# Flasher_2Ch_ISO_Astable.net
KiCad netlist of a schematic drawn in Altium Designer
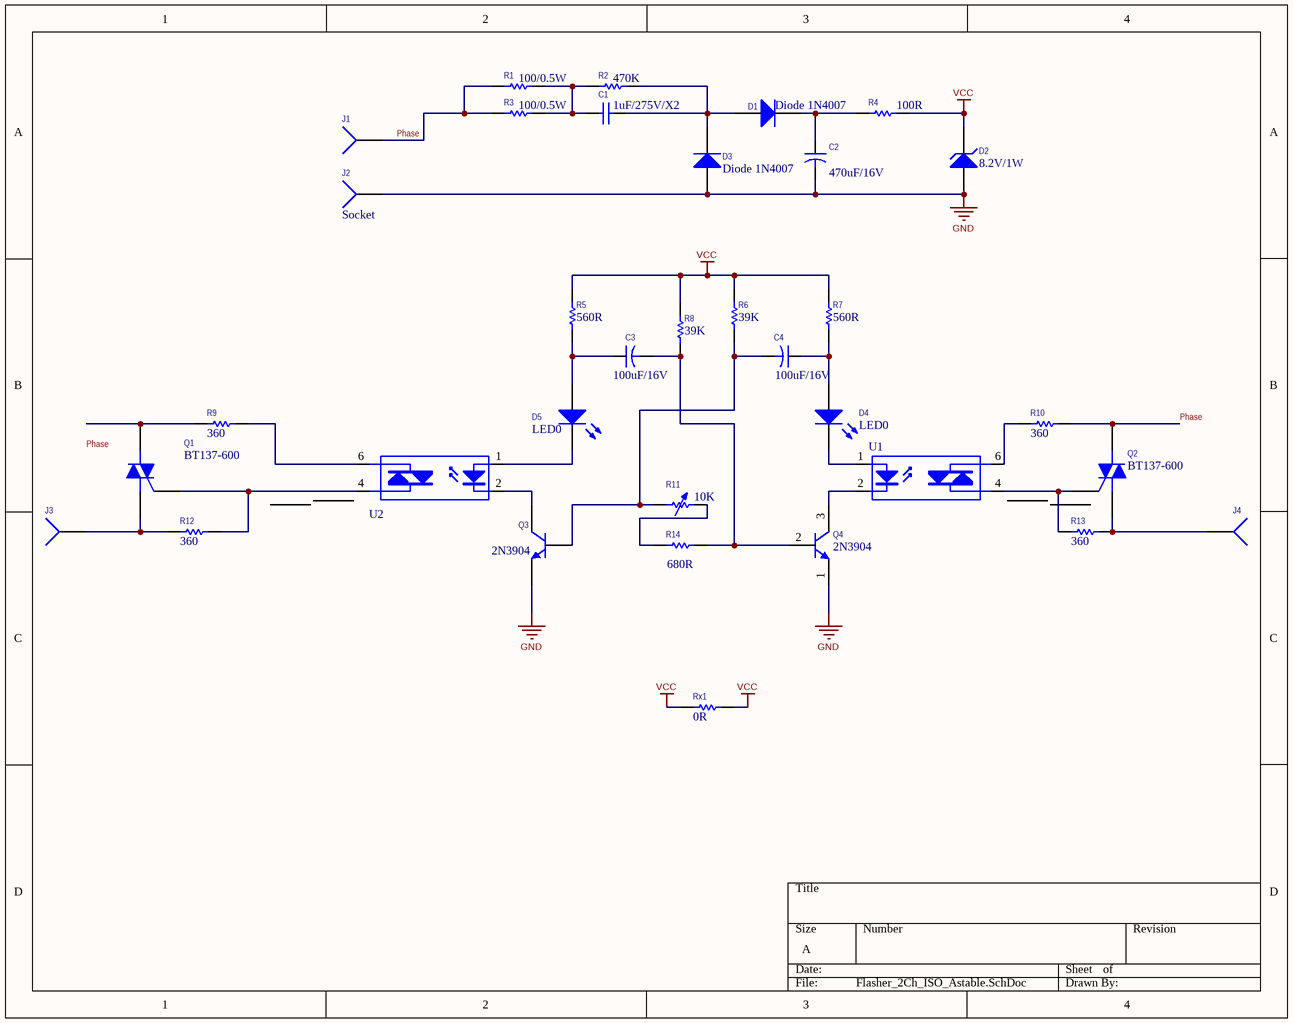
[diagram p0: Flasher_2Ch_ISO_Astable.SchDoc]

(export (version "E")
  (design (tool "Eeschema 10.0.6"))
  (components
    (comp (ref "C1")
      (value "1uF/275V/X2")
      (footprint "Cap_polyester_275V_P22.5")
      (description "Capacitor")
      (fields (field (name "Comment") "Cap") (field (name "PUBLISHER") "Altium Limited"))
      (libsource (lib "Miscellaneous Devices") (part "Cap"))
    )
    (comp (ref "C2")
      (value "470uF/16V")
      (footprint "Cap electrolitic radial 8x12-3.5")
      (description "Capacitor")
      (fields (field (name "Comment") "Cap2") (field (name "PUBLISHER") "Altium Limited"))
      (libsource (lib "Miscellaneous Devices") (part "Cap2"))
    )
    (comp (ref "C3")
      (value "100uF/16V")
      (footprint "Cap electrolitic radial 5x11-2")
      (description "Capacitor")
      (fields (field (name "Comment") "Cap2") (field (name "PUBLISHER") "Altium Limited"))
      (libsource (lib "Miscellaneous Devices") (part "Cap2"))
    )
    (comp (ref "C4")
      (value "100uF/16V")
      (footprint "Cap electrolitic radial 5x11-2")
      (description "Capacitor")
      (fields (field (name "Comment") "Cap2") (field (name "PUBLISHER") "Altium Limited"))
      (libsource (lib "Miscellaneous Devices") (part "Cap2"))
    )
    (comp (ref "D1")
      (value "Diode 1N4007")
      (footprint "DO-204AL")
      (description "1 Amp General Purpose Rectifier")
      (fields (field (name "PUBLISHER") "Altium Limited"))
      (libsource (lib "Miscellaneous Devices") (part "Diode 1N4007"))
    )
    (comp (ref "D2")
      (value "8.2V/1W")
      (footprint "DO-204AL")
      (description "Zener Diode")
      (fields (field (name "PUBLISHER") "Altium Limited"))
      (libsource (lib "Miscellaneous Devices") (part "D Zener"))
    )
    (comp (ref "D3")
      (value "Diode 1N4007")
      (footprint "DO-204AL")
      (description "1 Amp General Purpose Rectifier")
      (fields (field (name "PUBLISHER") "Altium Limited"))
      (libsource (lib "Miscellaneous Devices") (part "Diode 1N4007"))
    )
    (comp (ref "D4")
      (value "LED0")
      (footprint "LED5MM_RED")
      (description "Typical INFRARED GaAs LED")
      (fields (field (name "PUBLISHER") "Altium Limited"))
      (libsource (lib "Miscellaneous Devices") (part "LED0"))
    )
    (comp (ref "D5")
      (value "LED0")
      (footprint "LED5MM_RED")
      (description "Typical INFRARED GaAs LED")
      (fields (field (name "PUBLISHER") "Altium Limited"))
      (libsource (lib "Miscellaneous Devices") (part "LED0"))
    )
    (comp (ref "J1")
      (value "Socket")
      (footprint "PIN1")
      (fields (field (name "PUBLISHER") "Altium Limited"))
      (libsource (lib "Miscellaneous Connectors") (part "Socket"))
    )
    (comp (ref "J2")
      (value "Socket")
      (footprint "PIN1")
      (fields (field (name "PUBLISHER") "Altium Limited"))
      (libsource (lib "Miscellaneous Connectors") (part "Socket"))
    )
    (comp (ref "J3")
      (value "Socket")
      (footprint "PIN1")
      (fields (field (name "PUBLISHER") "Altium Limited"))
      (libsource (lib "Miscellaneous Connectors") (part "Socket"))
    )
    (comp (ref "J4")
      (value "Socket")
      (footprint "PIN1")
      (fields (field (name "PUBLISHER") "Altium Limited"))
      (libsource (lib "Miscellaneous Connectors") (part "Socket"))
    )
    (comp (ref "Q1")
      (value "BT137-600")
      (footprint "TO-220 AB with heatsink ya25")
      (description "Silicon Bidirectional Triode Thyristor")
      (fields (field (name "PUBLISHER") "Altium Limited"))
      (libsource (lib "Miscellaneous Devices") (part "Triac"))
    )
    (comp (ref "Q2")
      (value "BT137-600")
      (footprint "TO-220 AB with heatsink ya25")
      (description "Silicon Bidirectional Triode Thyristor")
      (fields (field (name "PUBLISHER") "Altium Limited"))
      (libsource (lib "Miscellaneous Devices") (part "Triac"))
    )
    (comp (ref "Q3")
      (value "2N3904")
      (footprint "TO-92 STR")
      (description "NPN General Purpose Amplifier")
      (fields (field (name "PUBLISHER") "Altium Limited"))
      (libsource (lib "") (part "2N3904_1"))
    )
    (comp (ref "Q4")
      (value "2N3904")
      (footprint "TO-92 STR")
      (description "NPN General Purpose Amplifier")
      (fields (field (name "PUBLISHER") "Altium Limited"))
      (libsource (lib "Miscellaneous Devices") (part "2N3904"))
    )
    (comp (ref "R1")
      (value "100/0.5W")
      (footprint "Axial 0_5W 5_0mm")
      (description "Resistor")
      (fields (field (name "Comment") "Res1") (field (name "PUBLISHER") "Altium Limited"))
      (libsource (lib "Miscellaneous Devices") (part "Res1"))
    )
    (comp (ref "R2")
      (value "470K")
      (footprint "Axial 0_25 W, 0_4 IN LEAD PITCH")
      (description "Resistor")
      (fields (field (name "Comment") "Res1") (field (name "PUBLISHER") "Altium Limited"))
      (libsource (lib "Miscellaneous Devices") (part "Res1"))
    )
    (comp (ref "R3")
      (value "100/0.5W")
      (footprint "Axial 0_5W 5_0mm")
      (description "Resistor")
      (fields (field (name "Comment") "Res1") (field (name "PUBLISHER") "Altium Limited"))
      (libsource (lib "Miscellaneous Devices") (part "Res1"))
    )
    (comp (ref "R4")
      (value "100R")
      (footprint "Axial 0_25 W, 0_4 IN LEAD PITCH")
      (description "Resistor")
      (fields (field (name "Comment") "Res1") (field (name "PUBLISHER") "Altium Limited"))
      (libsource (lib "Miscellaneous Devices") (part "Res1"))
    )
    (comp (ref "R5")
      (value "560R")
      (footprint "Axial 0_25 W, 0_4 IN LEAD PITCH")
      (description "Resistor")
      (fields (field (name "Comment") "Res1") (field (name "PUBLISHER") "Altium Limited"))
      (libsource (lib "Miscellaneous Devices") (part "Res1"))
    )
    (comp (ref "R6")
      (value "39K")
      (footprint "Axial 0_25 W, 0_4 IN LEAD PITCH")
      (description "Resistor")
      (fields (field (name "Comment") "Res1") (field (name "PUBLISHER") "Altium Limited"))
      (libsource (lib "Miscellaneous Devices") (part "Res1"))
    )
    (comp (ref "R7")
      (value "560R")
      (footprint "Axial 0_25 W, 0_4 IN LEAD PITCH")
      (description "Resistor")
      (fields (field (name "Comment") "Res1") (field (name "PUBLISHER") "Altium Limited"))
      (libsource (lib "Miscellaneous Devices") (part "Res1"))
    )
    (comp (ref "R8")
      (value "39K")
      (footprint "Axial 0_25 W, 0_4 IN LEAD PITCH")
      (description "Resistor")
      (fields (field (name "Comment") "Res1") (field (name "PUBLISHER") "Altium Limited"))
      (libsource (lib "Miscellaneous Devices") (part "Res1"))
    )
    (comp (ref "R9")
      (value "360")
      (footprint "Axial 0_25 W, 0_4 IN LEAD PITCH")
      (description "Resistor")
      (fields (field (name "Comment") "Res1") (field (name "PUBLISHER") "Altium Limited"))
      (libsource (lib "Miscellaneous Devices") (part "Res1"))
    )
    (comp (ref "R10")
      (value "360")
      (footprint "Axial 0_25 W, 0_4 IN LEAD PITCH")
      (description "Resistor")
      (fields (field (name "Comment") "Res1") (field (name "PUBLISHER") "Altium Limited"))
      (libsource (lib "Miscellaneous Devices") (part "Res1"))
    )
    (comp (ref "R11")
      (value "10K")
      (footprint "AXIAL-0.4")
      (description "Variable Resistor")
      (fields (field (name "Comment") "Res Adj1") (field (name "PUBLISHER") "Altium Limited"))
      (libsource (lib "Miscellaneous Devices") (part "Res Adj1"))
    )
    (comp (ref "R12")
      (value "360")
      (footprint "Axial 0_25 W, 0_4 IN LEAD PITCH")
      (description "Resistor")
      (fields (field (name "Comment") "Res1") (field (name "PUBLISHER") "Altium Limited"))
      (libsource (lib "Miscellaneous Devices") (part "Res1"))
    )
    (comp (ref "R13")
      (value "360")
      (footprint "Axial 0_25 W, 0_4 IN LEAD PITCH")
      (description "Resistor")
      (fields (field (name "Comment") "Res1") (field (name "PUBLISHER") "Altium Limited"))
      (libsource (lib "Miscellaneous Devices") (part "Res1"))
    )
    (comp (ref "R14")
      (value "680R")
      (footprint "Axial 0_25 W, 0_4 IN LEAD PITCH")
      (description "Resistor")
      (fields (field (name "Comment") "Res1") (field (name "PUBLISHER") "Altium Limited"))
      (libsource (lib "Miscellaneous Devices") (part "Res1"))
    )
    (comp (ref "Rx1")
      (value "0R")
      (footprint "axial-0.3")
      (description "Resistor")
      (fields (field (name "Comment") "Res1") (field (name "PUBLISHER") "Altium Limited"))
      (libsource (lib "Miscellaneous Devices") (part "Res1"))
    )
    (comp (ref "U1")
      (value "MOC3063")
      (footprint "DIP-6")
      (description "Opto-Triac")
      (fields (field (name "PUBLISHER") "Altium Limited"))
      (libsource (lib "Miscellaneous Devices") (part "Opto TRIAC"))
    )
    (comp (ref "U2")
      (value "MOC3063")
      (footprint "DIP-6")
      (description "Opto-Triac")
      (fields (field (name "PUBLISHER") "Altium Limited"))
      (libsource (lib "Miscellaneous Devices") (part "Opto TRIAC"))
    )
  )
  (nets
    (net (code "1") (name "/Phase") (class "Default")
      (node (ref "J1") (pin "1") (pinfunction "1_1") (pintype "passive"))
      (node (ref "Q2") (pin "2") (pinfunction "M2_2") (pintype "passive"))
      (node (ref "R1") (pin "1") (pinfunction "1_1") (pintype "passive"))
      (node (ref "R10") (pin "1") (pinfunction "1_1") (pintype "passive"))
      (node (ref "R3") (pin "1") (pinfunction "1_1") (pintype "passive"))
    )
    (net (code "2") (name "GND") (class "Default")
      (node (ref "C2") (pin "2") (pinfunction "2_2") (pintype "passive"))
      (node (ref "D2") (pin "1") (pinfunction "A_1") (pintype "passive"))
      (node (ref "D3") (pin "1") (pinfunction "A_1") (pintype "passive"))
      (node (ref "J2") (pin "1") (pinfunction "1_1") (pintype "passive"))
      (node (ref "Q3") (pin "1") (pinfunction "E_1") (pintype "passive"))
      (node (ref "Q4") (pin "1") (pinfunction "E_1") (pintype "passive"))
    )
    (net (code "3") (name "Net-(C1-Pad1)") (class "Default")
      (node (ref "C1") (pin "1") (pinfunction "1_1") (pintype "passive"))
      (node (ref "R1") (pin "2") (pinfunction "2_2") (pintype "passive"))
      (node (ref "R2") (pin "1") (pinfunction "1_1") (pintype "passive"))
      (node (ref "R3") (pin "2") (pinfunction "2_2") (pintype "passive"))
    )
    (net (code "4") (name "Net-(D1-A)") (class "Default")
      (node (ref "C1") (pin "2") (pinfunction "2_2") (pintype "passive"))
      (node (ref "D1") (pin "1") (pinfunction "A_1") (pintype "passive"))
      (node (ref "D3") (pin "2") (pinfunction "K_2") (pintype "passive"))
      (node (ref "R2") (pin "2") (pinfunction "2_2") (pintype "passive"))
    )
    (net (code "5") (name "Net-(D1-K)") (class "Default")
      (node (ref "C2") (pin "1") (pinfunction "1_1") (pintype "passive"))
      (node (ref "D1") (pin "2") (pinfunction "K_2") (pintype "passive"))
      (node (ref "R4") (pin "2") (pinfunction "2_2") (pintype "passive"))
    )
    (net (code "6") (name "Net-(D4-A)") (class "Default")
      (node (ref "C4") (pin "1") (pinfunction "1_1") (pintype "passive"))
      (node (ref "D4") (pin "1") (pinfunction "A_1") (pintype "passive"))
      (node (ref "R7") (pin "1") (pinfunction "1_1") (pintype "passive"))
    )
    (net (code "7") (name "Net-(D4-K)") (class "Default")
      (node (ref "D4") (pin "2") (pinfunction "K_2") (pintype "passive"))
      (node (ref "U1") (pin "1") (pinfunction "A_1") (pintype "passive"))
    )
    (net (code "8") (name "Net-(D5-A)") (class "Default")
      (node (ref "C3") (pin "1") (pinfunction "1_1") (pintype "passive"))
      (node (ref "D5") (pin "1") (pinfunction "A_1") (pintype "passive"))
      (node (ref "R5") (pin "1") (pinfunction "1_1") (pintype "passive"))
    )
    (net (code "9") (name "Net-(D5-K)") (class "Default")
      (node (ref "D5") (pin "2") (pinfunction "K_2") (pintype "passive"))
      (node (ref "U2") (pin "1") (pinfunction "A_1") (pintype "passive"))
    )
    (net (code "10") (name "Net-(Q1-G)") (class "Default")
      (node (ref "Q1") (pin "3") (pinfunction "G_3") (pintype "passive"))
      (node (ref "R12") (pin "1") (pinfunction "1_1") (pintype "passive"))
      (node (ref "U2") (pin "4") (pinfunction "A/K_4") (pintype "passive"))
    )
    (net (code "11") (name "Net-(Q1-M1)") (class "Default")
      (node (ref "J3") (pin "1") (pinfunction "1_1") (pintype "passive"))
      (node (ref "Q1") (pin "1") (pinfunction "M1_1") (pintype "passive"))
      (node (ref "R12") (pin "2") (pinfunction "2_2") (pintype "passive"))
    )
    (net (code "12") (name "Net-(Q1-M2)") (class "Default")
      (node (ref "Q1") (pin "2") (pinfunction "M2_2") (pintype "passive"))
      (node (ref "R9") (pin "2") (pinfunction "2_2") (pintype "passive"))
    )
    (net (code "13") (name "Net-(Q2-G)") (class "Default")
      (node (ref "Q2") (pin "3") (pinfunction "G_3") (pintype "passive"))
      (node (ref "R13") (pin "2") (pinfunction "2_2") (pintype "passive"))
      (node (ref "U1") (pin "4") (pinfunction "A/K_4") (pintype "passive"))
    )
    (net (code "14") (name "Net-(Q2-M1)") (class "Default")
      (node (ref "J4") (pin "1") (pinfunction "1_1") (pintype "passive"))
      (node (ref "Q2") (pin "1") (pinfunction "M1_1") (pintype "passive"))
      (node (ref "R13") (pin "1") (pinfunction "1_1") (pintype "passive"))
    )
    (net (code "15") (name "Net-(Q3-B)") (class "Default")
      (node (ref "C4") (pin "2") (pinfunction "2_2") (pintype "passive"))
      (node (ref "Q3") (pin "2") (pinfunction "B_2") (pintype "passive"))
      (node (ref "R11") (pin "1") (pinfunction "1_1") (pintype "passive"))
      (node (ref "R6") (pin "1") (pinfunction "1_1") (pintype "passive"))
    )
    (net (code "16") (name "Net-(Q3-C)") (class "Default")
      (node (ref "Q3") (pin "3") (pinfunction "C_3") (pintype "passive"))
      (node (ref "U2") (pin "2") (pinfunction "K_2") (pintype "passive"))
    )
    (net (code "17") (name "Net-(Q4-B)") (class "Default")
      (node (ref "C3") (pin "2") (pinfunction "2_2") (pintype "passive"))
      (node (ref "Q4") (pin "2") (pinfunction "B_2") (pintype "passive"))
      (node (ref "R14") (pin "1") (pinfunction "1_1") (pintype "passive"))
      (node (ref "R8") (pin "1") (pinfunction "1_1") (pintype "passive"))
    )
    (net (code "18") (name "Net-(Q4-C)") (class "Default")
      (node (ref "Q4") (pin "3") (pinfunction "C_3") (pintype "passive"))
      (node (ref "U1") (pin "2") (pinfunction "K_2") (pintype "passive"))
    )
    (net (code "19") (name "Net-(R9-Pad1)") (class "Default")
      (node (ref "R9") (pin "1") (pinfunction "1_1") (pintype "passive"))
      (node (ref "U2") (pin "6") (pinfunction "A/K_6") (pintype "passive"))
    )
    (net (code "20") (name "Net-(R10-Pad2)") (class "Default")
      (node (ref "R10") (pin "2") (pinfunction "2_2") (pintype "passive"))
      (node (ref "U1") (pin "6") (pinfunction "A/K_6") (pintype "passive"))
    )
    (net (code "21") (name "Net-(R11-Pad2)") (class "Default")
      (node (ref "R11") (pin "2") (pinfunction "2_2") (pintype "passive"))
      (node (ref "R14") (pin "2") (pinfunction "2_2") (pintype "passive"))
    )
    (net (code "22") (name "VCC") (class "Default")
      (node (ref "D2") (pin "2") (pinfunction "K_2") (pintype "passive"))
      (node (ref "R4") (pin "1") (pinfunction "1_1") (pintype "passive"))
      (node (ref "R5") (pin "2") (pinfunction "2_2") (pintype "passive"))
      (node (ref "R6") (pin "2") (pinfunction "2_2") (pintype "passive"))
      (node (ref "R7") (pin "2") (pinfunction "2_2") (pintype "passive"))
      (node (ref "R8") (pin "2") (pinfunction "2_2") (pintype "passive"))
      (node (ref "Rx1") (pin "1") (pinfunction "1_1") (pintype "passive"))
      (node (ref "Rx1") (pin "2") (pinfunction "2_2") (pintype "passive"))
    )
    (net (code "23") (name "unconnected-(U1-NC-Pad3)") (class "Default")
      (node (ref "U1") (pin "3") (pinfunction "NC_3") (pintype "passive"))
    )
    (net (code "24") (name "unconnected-(U1-NC-Pad5)") (class "Default")
      (node (ref "U1") (pin "5") (pinfunction "NC_5") (pintype "passive"))
    )
    (net (code "25") (name "unconnected-(U2-NC-Pad3)") (class "Default")
      (node (ref "U2") (pin "3") (pinfunction "NC_3") (pintype "passive"))
    )
    (net (code "26") (name "unconnected-(U2-NC-Pad5)") (class "Default")
      (node (ref "U2") (pin "5") (pinfunction "NC_5") (pintype "passive"))
    )
  )
)
